# SignalMast-ColorLight-Dwarf.net
KiCad netlist of a schematic drawn in EAGLE
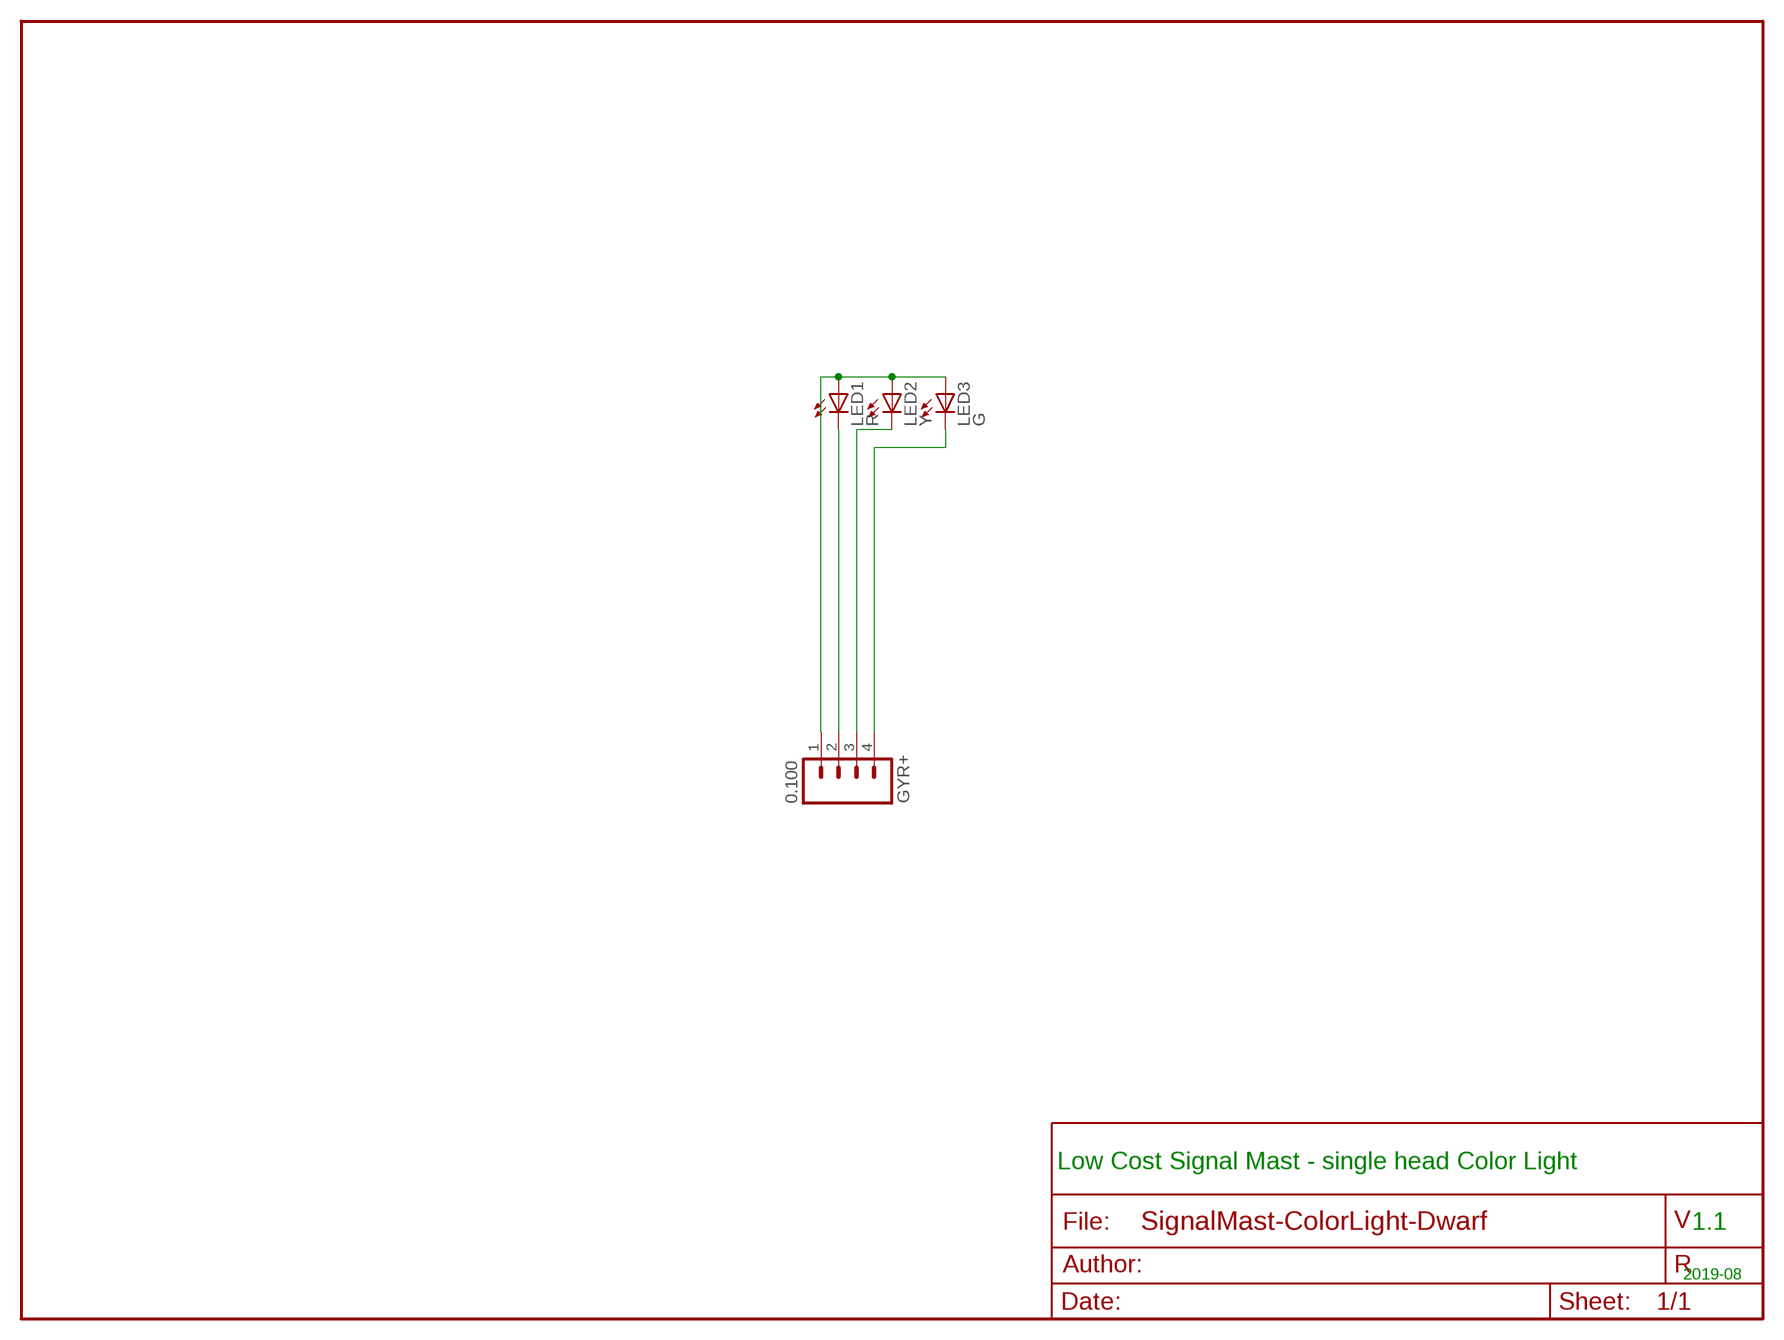
[diagram p0: schematic, sheet 1]

(export (version "E")
  (design (tool "Eeschema 10.0.6"))
  (components
    (comp (ref "GYR+")
      (value "0.100")
      (footprint "eagle-import:1X04_LOCK")
      (libsource (lib "eagle-import") (part "CONNECTOR-M04LOCK"))
    )
    (comp (ref "LED1")
      (value "R")
      (footprint "eagle-import:0603-LED")
      (libsource (lib "eagle-import") (part "LED0603-LED"))
    )
    (comp (ref "LED2")
      (value "Y")
      (footprint "eagle-import:0603-LED")
      (libsource (lib "eagle-import") (part "LED0603-LED"))
    )
    (comp (ref "LED3")
      (value "G")
      (footprint "eagle-import:0603-LED")
      (libsource (lib "eagle-import") (part "LED0603-LED"))
    )
  )
  (nets
    (net (code "1") (name "Net-(GYR+-Pad1)") (class "Default")
      (node (ref "GYR+") (pin "1") (pinfunction "1_1") (pintype "passive"))
      (node (ref "LED1") (pin "A") (pinfunction "A_A") (pintype "passive"))
      (node (ref "LED2") (pin "A") (pinfunction "A_A") (pintype "passive"))
      (node (ref "LED3") (pin "A") (pinfunction "A_A") (pintype "passive"))
    )
    (net (code "2") (name "Net-(GYR+-Pad2)") (class "Default")
      (node (ref "GYR+") (pin "2") (pinfunction "2_2") (pintype "passive"))
      (node (ref "LED1") (pin "C") (pinfunction "C_C") (pintype "passive"))
    )
    (net (code "3") (name "Net-(GYR+-Pad3)") (class "Default")
      (node (ref "GYR+") (pin "3") (pinfunction "3_3") (pintype "passive"))
      (node (ref "LED2") (pin "C") (pinfunction "C_C") (pintype "passive"))
    )
    (net (code "4") (name "Net-(GYR+-Pad4)") (class "Default")
      (node (ref "GYR+") (pin "4") (pinfunction "4_4") (pintype "passive"))
      (node (ref "LED3") (pin "C") (pinfunction "C_C") (pintype "passive"))
    )
  )
)
